# Fly_Buck_Power_Supply_for_Inverter.net
KiCad netlist of a schematic drawn in Altium Designer
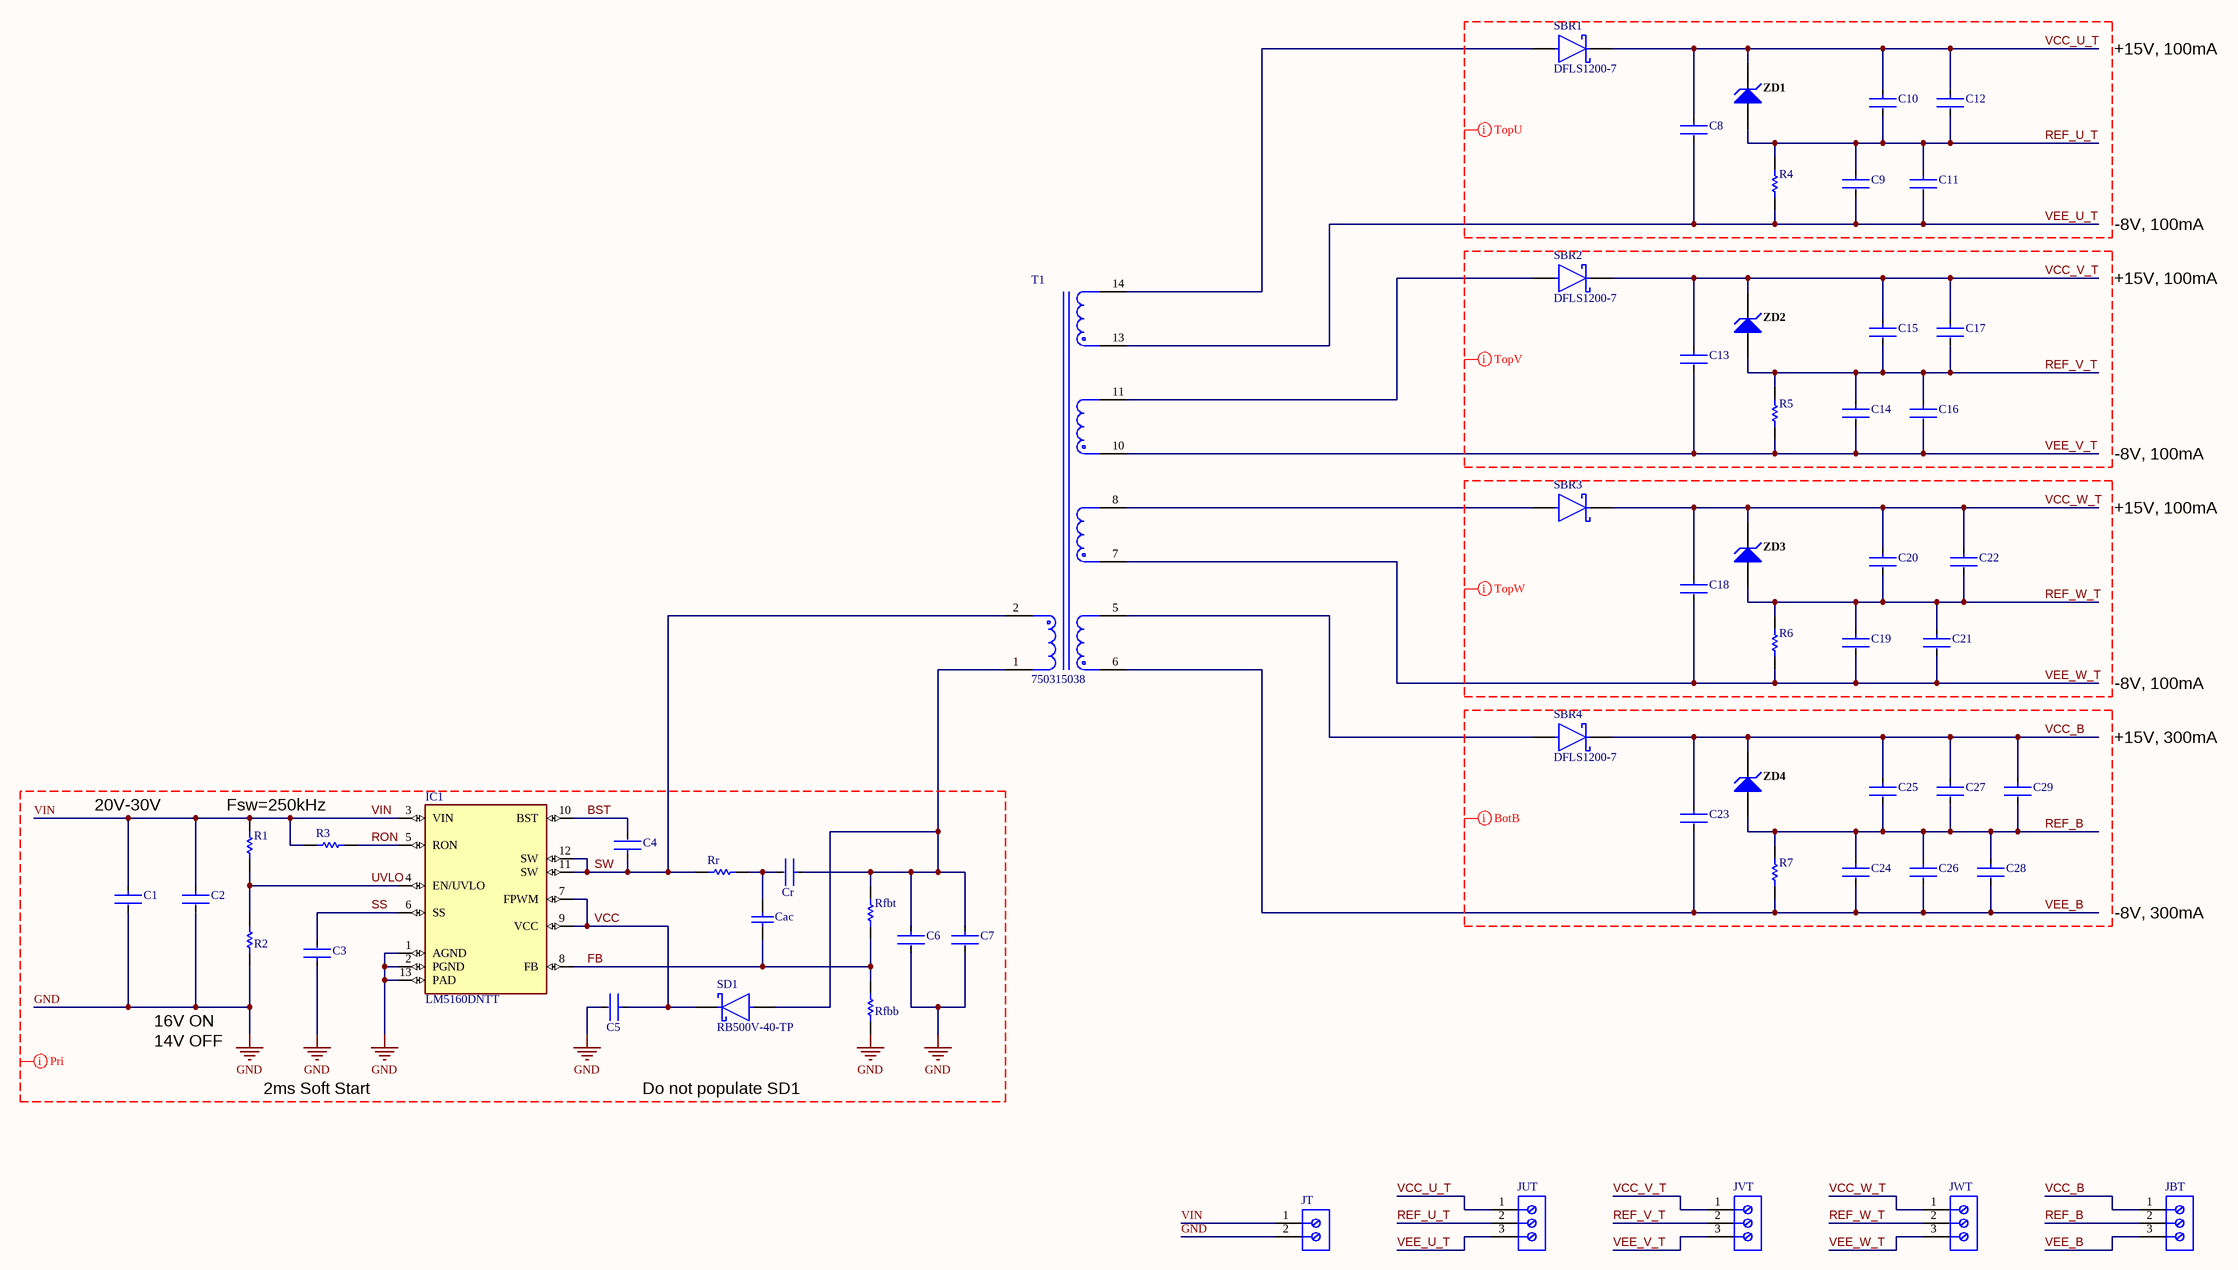
[diagram p0: Fly_Buck_Power_Supply_for_Inverter.SchDoc]

(export (version "E")
  (design (tool "Eeschema 10.0.6"))
  (components
    (comp (ref "C1")
      (value "GRM32ER71H106KA12L")
      (footprint "FP-GRM32-MFG")
      (description "CAP CER 10µF 50V X7R 1210")
      (fields (field (name "TOLERANCE") "10%") (field (name "MANUFACTURER") "Murata"))
      (libsource (lib "Altium Content Vault") (part "11868f565c42a9108669ba33697ecf6"))
    )
    (comp (ref "C2")
      (value "C0603X104K5RACTU")
      (footprint "FP-C0603-CJ-MFG")
      (description "CAP CER 0.1µF 50V X7R 0603")
      (fields (field (name "VOLTAGE") "50V") (field (name "MANUFACTURER") "Kemet"))
      (libsource (lib "Altium Content Vault") (part "11868f565c42a9108669ba33697ecf6"))
    )
    (comp (ref "C3")
      (value "C1608X7R1H103K080AA")
      (footprint "FP-C1608-080-0_1-MFG")
      (description "Multilayer Ceramic Capacitors 0.01µF ±10% 50V X7R SMD 0603")
      (fields (field (name "VOLTAGE") "50V") (field (name "TOLERANCE") "10%"))
      (libsource (lib "Altium Content Vault") (part "236180d848d6139a670b325ea6854c9"))
    )
    (comp (ref "C4")
      (value "C1608X7R1H103K080AA")
      (footprint "FP-C1608-080-0_1-MFG")
      (description "Multilayer Ceramic Capacitors 0.01µF ±10% 50V X7R SMD 0603")
      (fields (field (name "VOLTAGE") "50V") (field (name "TOLERANCE") "10%"))
      (libsource (lib "Altium Content Vault") (part "236180d848d6139a670b325ea6854c9"))
    )
    (comp (ref "C5")
      (value "C1608X5R1E105K080AC")
      (footprint "FP-C1608-080-0_1-MFG")
      (description "Multilayer Ceramic Capacitors 1μF ±10% 25V X5R SMD 0603")
      (fields (field (name "TOLERANCE") "10%"))
      (libsource (lib "Altium Content Vault") (part "236180d848d6139a670b325ea6854c9"))
    )
    (comp (ref "C6")
      (value "GRM32ER71E226KE15L")
      (footprint "FP-GRM32E-0_3-0_2-IPC_B")
      (description "Chip Multilayer Ceramic Capacitors for General Purpose, 1210, 22µF, X7R, 15%, 10%, 25V")
      (fields (field (name "VOLTAGE") "25V") (field (name "TOLERANCE") "10%"))
      (libsource (lib "Altium Content Vault") (part "02cd4be3c70576c341d710602a673aa"))
    )
    (comp (ref "C7")
      (value "GRM32ER71E226KE15L")
      (footprint "FP-GRM32E-0_3-0_2-IPC_B")
      (description "Chip Multilayer Ceramic Capacitors for General Purpose, 1210, 22µF, X7R, 15%, 10%, 25V")
      (fields (field (name "VOLTAGE") "25V") (field (name "TOLERANCE") "10%"))
      (libsource (lib "Altium Content Vault") (part "02cd4be3c70576c341d710602a673aa"))
    )
    (comp (ref "C8")
      (value "GRM32ER71H106KA12L")
      (footprint "FP-GRM32-MFG")
      (description "CAP CER 10µF 50V X7R 1210")
      (fields (field (name "TOLERANCE") "10%") (field (name "MANUFACTURER") "Murata"))
      (libsource (lib "Altium Content Vault") (part "11868f565c42a9108669ba33697ecf6"))
    )
    (comp (ref "C9")
      (value "GRM32ER71E226KE15L")
      (footprint "FP-GRM32E-0_3-0_2-IPC_B")
      (description "Chip Multilayer Ceramic Capacitors for General Purpose, 1210, 22µF, X7R, 15%, 10%, 25V")
      (fields (field (name "VOLTAGE") "25V") (field (name "TOLERANCE") "10%"))
      (libsource (lib "Altium Content Vault") (part "02cd4be3c70576c341d710602a673aa"))
    )
    (comp (ref "C10")
      (value "GRM32ER71E226KE15L")
      (footprint "FP-GRM32E-0_3-0_2-IPC_B")
      (description "Chip Multilayer Ceramic Capacitors for General Purpose, 1210, 22µF, X7R, 15%, 10%, 25V")
      (fields (field (name "VOLTAGE") "25V") (field (name "TOLERANCE") "10%"))
      (libsource (lib "Altium Content Vault") (part "02cd4be3c70576c341d710602a673aa"))
    )
    (comp (ref "C11")
      (value "C0603X104K5RACTU")
      (footprint "FP-C0603-CJ-MFG")
      (description "CAP CER 0.1µF 50V X7R 0603")
      (fields (field (name "VOLTAGE") "50V") (field (name "MANUFACTURER") "Kemet"))
      (libsource (lib "Altium Content Vault") (part "11868f565c42a9108669ba33697ecf6"))
    )
    (comp (ref "C12")
      (value "C0603X104K5RACTU")
      (footprint "FP-C0603-CJ-MFG")
      (description "CAP CER 0.1µF 50V X7R 0603")
      (fields (field (name "VOLTAGE") "50V") (field (name "MANUFACTURER") "Kemet"))
      (libsource (lib "Altium Content Vault") (part "11868f565c42a9108669ba33697ecf6"))
    )
    (comp (ref "C13")
      (value "GRM32ER71H106KA12L")
      (footprint "FP-GRM32-MFG")
      (description "CAP CER 10µF 50V X7R 1210")
      (fields (field (name "TOLERANCE") "10%") (field (name "MANUFACTURER") "Murata"))
      (libsource (lib "Altium Content Vault") (part "11868f565c42a9108669ba33697ecf6"))
    )
    (comp (ref "C14")
      (value "GRM32ER71E226KE15L")
      (footprint "FP-GRM32E-0_3-0_2-IPC_B")
      (description "Chip Multilayer Ceramic Capacitors for General Purpose, 1210, 22µF, X7R, 15%, 10%, 25V")
      (fields (field (name "VOLTAGE") "25V") (field (name "TOLERANCE") "10%"))
      (libsource (lib "Altium Content Vault") (part "02cd4be3c70576c341d710602a673aa"))
    )
    (comp (ref "C15")
      (value "GRM32ER71E226KE15L")
      (footprint "FP-GRM32E-0_3-0_2-IPC_B")
      (description "Chip Multilayer Ceramic Capacitors for General Purpose, 1210, 22µF, X7R, 15%, 10%, 25V")
      (fields (field (name "VOLTAGE") "25V") (field (name "TOLERANCE") "10%"))
      (libsource (lib "Altium Content Vault") (part "02cd4be3c70576c341d710602a673aa"))
    )
    (comp (ref "C16")
      (value "C0603X104K5RACTU")
      (footprint "FP-C0603-CJ-MFG")
      (description "CAP CER 0.1µF 50V X7R 0603")
      (fields (field (name "VOLTAGE") "50V") (field (name "MANUFACTURER") "Kemet"))
      (libsource (lib "Altium Content Vault") (part "11868f565c42a9108669ba33697ecf6"))
    )
    (comp (ref "C17")
      (value "C0603X104K5RACTU")
      (footprint "FP-C0603-CJ-MFG")
      (description "CAP CER 0.1µF 50V X7R 0603")
      (fields (field (name "VOLTAGE") "50V") (field (name "MANUFACTURER") "Kemet"))
      (libsource (lib "Altium Content Vault") (part "11868f565c42a9108669ba33697ecf6"))
    )
    (comp (ref "C18")
      (value "GRM32ER71H106KA12L")
      (footprint "FP-GRM32-MFG")
      (description "CAP CER 10µF 50V X7R 1210")
      (fields (field (name "TOLERANCE") "10%") (field (name "MANUFACTURER") "Murata"))
      (libsource (lib "Altium Content Vault") (part "11868f565c42a9108669ba33697ecf6"))
    )
    (comp (ref "C19")
      (value "GRM32ER71E226KE15L")
      (footprint "FP-GRM32E-0_3-0_2-IPC_B")
      (description "Chip Multilayer Ceramic Capacitors for General Purpose, 1210, 22µF, X7R, 15%, 10%, 25V")
      (fields (field (name "VOLTAGE") "25V") (field (name "TOLERANCE") "10%"))
      (libsource (lib "Altium Content Vault") (part "02cd4be3c70576c341d710602a673aa"))
    )
    (comp (ref "C20")
      (value "GRM32ER71E226KE15L")
      (footprint "FP-GRM32E-0_3-0_2-IPC_B")
      (description "Chip Multilayer Ceramic Capacitors for General Purpose, 1210, 22µF, X7R, 15%, 10%, 25V")
      (fields (field (name "VOLTAGE") "25V") (field (name "TOLERANCE") "10%"))
      (libsource (lib "Altium Content Vault") (part "02cd4be3c70576c341d710602a673aa"))
    )
    (comp (ref "C21")
      (value "C0603X104K5RACTU")
      (footprint "FP-C0603-CJ-MFG")
      (description "CAP CER 0.1µF 50V X7R 0603")
      (fields (field (name "VOLTAGE") "50V") (field (name "MANUFACTURER") "Kemet"))
      (libsource (lib "Altium Content Vault") (part "11868f565c42a9108669ba33697ecf6"))
    )
    (comp (ref "C22")
      (value "C0603X104K5RACTU")
      (footprint "FP-C0603-CJ-MFG")
      (description "CAP CER 0.1µF 50V X7R 0603")
      (fields (field (name "VOLTAGE") "50V") (field (name "MANUFACTURER") "Kemet"))
      (libsource (lib "Altium Content Vault") (part "11868f565c42a9108669ba33697ecf6"))
    )
    (comp (ref "C23")
      (value "GRM32ER71H106KA12L")
      (footprint "FP-GRM32-MFG")
      (description "CAP CER 10µF 50V X7R 1210")
      (fields (field (name "TOLERANCE") "10%") (field (name "MANUFACTURER") "Murata"))
      (libsource (lib "Altium Content Vault") (part "11868f565c42a9108669ba33697ecf6"))
    )
    (comp (ref "C24")
      (value "GRM32ER71E226KE15L")
      (footprint "FP-GRM32E-0_3-0_2-IPC_B")
      (description "Chip Multilayer Ceramic Capacitors for General Purpose, 1210, 22µF, X7R, 15%, 10%, 25V")
      (fields (field (name "VOLTAGE") "25V") (field (name "TOLERANCE") "10%"))
      (libsource (lib "Altium Content Vault") (part "02cd4be3c70576c341d710602a673aa"))
    )
    (comp (ref "C25")
      (value "GRM32ER71E226KE15L")
      (footprint "FP-GRM32E-0_3-0_2-IPC_B")
      (description "Chip Multilayer Ceramic Capacitors for General Purpose, 1210, 22µF, X7R, 15%, 10%, 25V")
      (fields (field (name "VOLTAGE") "25V") (field (name "TOLERANCE") "10%"))
      (libsource (lib "Altium Content Vault") (part "02cd4be3c70576c341d710602a673aa"))
    )
    (comp (ref "C26")
      (value "GRM32ER71E226KE15L")
      (footprint "FP-GRM32E-0_3-0_2-IPC_B")
      (description "Chip Multilayer Ceramic Capacitors for General Purpose, 1210, 22µF, X7R, 15%, 10%, 25V")
      (fields (field (name "VOLTAGE") "25V") (field (name "TOLERANCE") "10%"))
      (libsource (lib "Altium Content Vault") (part "02cd4be3c70576c341d710602a673aa"))
    )
    (comp (ref "C27")
      (value "GRM32ER71E226KE15L")
      (footprint "FP-GRM32E-0_3-0_2-IPC_B")
      (description "Chip Multilayer Ceramic Capacitors for General Purpose, 1210, 22µF, X7R, 15%, 10%, 25V")
      (fields (field (name "VOLTAGE") "25V") (field (name "TOLERANCE") "10%"))
      (libsource (lib "Altium Content Vault") (part "02cd4be3c70576c341d710602a673aa"))
    )
    (comp (ref "C28")
      (value "C0603X104K5RACTU")
      (footprint "FP-C0603-CJ-MFG")
      (description "CAP CER 0.1µF 50V X7R 0603")
      (fields (field (name "VOLTAGE") "50V") (field (name "MANUFACTURER") "Kemet"))
      (libsource (lib "Altium Content Vault") (part "11868f565c42a9108669ba33697ecf6"))
    )
    (comp (ref "C29")
      (value "C0603X104K5RACTU")
      (footprint "FP-C0603-CJ-MFG")
      (description "CAP CER 0.1µF 50V X7R 0603")
      (fields (field (name "VOLTAGE") "50V") (field (name "MANUFACTURER") "Kemet"))
      (libsource (lib "Altium Content Vault") (part "11868f565c42a9108669ba33697ecf6"))
    )
    (comp (ref "Cac")
      (value "C0603X102K5RACTU")
      (footprint "CAPC1608X87X35NL20T15")
      (description "Multilayer Ceramic Capacitor, 1000 pF, 50 V, ± 10%, X7R, 0603 [1608 Metric]")
      (fields (field (name "MANUFACTURER") "Kemet"))
      (libsource (lib "Altium Content Vault") (part "CAP"))
    )
    (comp (ref "Cr")
      (value "C1608X7R1H103K080AA")
      (footprint "FP-C1608-080-0_1-MFG")
      (description "Multilayer Ceramic Capacitors 0.01µF ±10% 50V X7R SMD 0603")
      (fields (field (name "VOLTAGE") "50V") (field (name "TOLERANCE") "10%"))
      (libsource (lib "Altium Content Vault") (part "236180d848d6139a670b325ea6854c9"))
    )
    (comp (ref "IC1")
      (value "LM5160DNTT")
      (footprint "LM5160DNTT:FP-DNT0012B-IPC_B")
      (description "LM5160 wide input 65V, 2A synchronous buck/Fly-Buck converter 12-WSON -40 to 125")
      (libsource (lib "LM5160DNTT") (part "LM5160DNTT"))
    )
    (comp (ref "JBT")
      (value "691214110003")
      (footprint "691214110003")
      (description "Conn Terminal Block 3 POS 3.5mm Solder ST Thru-Hole 10A Box")
      (fields (field (name "VOLTAGE") "300V"))
      (libsource (lib "Altium Content Vault") (part "TBL - 1R - 03P - Screw"))
    )
    (comp (ref "JT")
      (value "691214110002")
      (footprint "691214110002")
      (description "Conn Terminal Block 2 POS 3.5mm Solder ST Thru-Hole 10A Box")
      (fields (field (name "VOLTAGE") "300V"))
      (libsource (lib "Altium Content Vault") (part "TBL - 1R - 02P - Screw"))
    )
    (comp (ref "JUT")
      (value "691214110003")
      (footprint "691214110003")
      (description "Conn Terminal Block 3 POS 3.5mm Solder ST Thru-Hole 10A Box")
      (fields (field (name "VOLTAGE") "300V"))
      (libsource (lib "Altium Content Vault") (part "TBL - 1R - 03P - Screw"))
    )
    (comp (ref "JVT")
      (value "691214110003")
      (footprint "691214110003")
      (description "Conn Terminal Block 3 POS 3.5mm Solder ST Thru-Hole 10A Box")
      (fields (field (name "VOLTAGE") "300V"))
      (libsource (lib "Altium Content Vault") (part "TBL - 1R - 03P - Screw"))
    )
    (comp (ref "JWT")
      (value "691214110003")
      (footprint "691214110003")
      (description "Conn Terminal Block 3 POS 3.5mm Solder ST Thru-Hole 10A Box")
      (fields (field (name "VOLTAGE") "300V"))
      (libsource (lib "Altium Content Vault") (part "TBL - 1R - 03P - Screw"))
    )
    (comp (ref "R1")
      (value "RK73H1JTTD1003F")
      (footprint "RESC1608X55X30ML20T10")
      (description "Res Thick Film 0603 100K Ohm 1% 0.1W(1/10W) ±100ppm/C Pad SMD Automotive T/R")
      (fields (field (name "MANUFACTURER") "KOA Speer"))
      (libsource (lib "Altium Content Vault") (part "RES"))
    )
    (comp (ref "R2")
      (value "CRCW06038K45FKEA")
      (footprint "RESC1609X50X30LL10T20")
      (description "SMD Chip Resistor, 8.45K Ohm, ± 1%, 100 mW, 0603 [1608 Metric], Thick Film, General Purpose")
      (fields (field (name "MANUFACTURER") "Vishay Dale"))
      (libsource (lib "Altium Content Vault") (part "RES"))
    )
    (comp (ref "R3")
      (value "RC0603FR-07453RL")
      (footprint "RESC1608X55X25NL10T15")
      (description "SMD Chip Resistor, 453 Ohm, ± 1%, 100 mW, 0603 [1608 Metric], Thick Film, General Purpos")
      (fields (field (name "MANUFACTURER") "Yageo"))
      (libsource (lib "Altium Content Vault") (part "RES"))
    )
    (comp (ref "R4")
      (value "ERJ-6ENF5110V")
      (footprint "RESC2013X70X40ML20T20")
      (description "SMD Chip Resistor, 511 Ohm, ± 1%, 125 mW, 0805 [2012 Metric], Thick Film, Precision")
      (fields (field (name "MANUFACTURER") "Panasonic"))
      (libsource (lib "Altium Content Vault") (part "RES"))
    )
    (comp (ref "R5")
      (value "ERJ-6ENF5110V")
      (footprint "RESC2013X70X40ML20T20")
      (description "SMD Chip Resistor, 511 Ohm, ± 1%, 125 mW, 0805 [2012 Metric], Thick Film, Precision")
      (fields (field (name "MANUFACTURER") "Panasonic"))
      (libsource (lib "Altium Content Vault") (part "RES"))
    )
    (comp (ref "R6")
      (value "ERJ-6ENF5110V")
      (footprint "RESC2013X70X40ML20T20")
      (description "SMD Chip Resistor, 511 Ohm, ± 1%, 125 mW, 0805 [2012 Metric], Thick Film, Precision")
      (fields (field (name "MANUFACTURER") "Panasonic"))
      (libsource (lib "Altium Content Vault") (part "RES"))
    )
    (comp (ref "R7")
      (value "ERJ-6ENF5110V")
      (footprint "RESC2013X70X40ML20T20")
      (description "SMD Chip Resistor, 511 Ohm, ± 1%, 125 mW, 0805 [2012 Metric], Thick Film, Precision")
      (fields (field (name "MANUFACTURER") "Panasonic"))
      (libsource (lib "Altium Content Vault") (part "RES"))
    )
    (comp (ref "Rfbb")
      (value "ERA3AEB2052V")
      (footprint "RESC1608X55X30ML20T20")
      (description "Res Thin Film 0603 20.5K Ohm 0.1% 0.1W(1/10W) ±25ppm/C Pad SMD Automotive T/R")
      (fields (field (name "MANUFACTURER") "Panasonic"))
      (libsource (lib "Altium Content Vault") (part "RES"))
    )
    (comp (ref "Rfbt")
      (value "ERJ-3EKF8662V")
      (footprint "RESC1608X55X30NL15T15")
      (fields (field (name "MANUFACTURER") "Panasonic"))
      (libsource (lib "Altium Content Vault") (part "RES"))
    )
    (comp (ref "Rr")
      (value "ERA3AEB2052V")
      (footprint "RESC1608X55X30ML20T20")
      (description "Res Thin Film 0603 20.5K Ohm 0.1% 0.1W(1/10W) ±25ppm/C Pad SMD Automotive T/R")
      (fields (field (name "MANUFACTURER") "Panasonic"))
      (libsource (lib "Altium Content Vault") (part "RES"))
    )
    (comp (ref "SBR1")
      (value "DFLS1200-7")
      (footprint "FP-PowerDI123-MFG")
      (description "Rectifier Diode, Schottky, 200V, 1A")
      (fields
        (field (name "MANUFACTURER") "Diodes Inc.")
        (field (name "OCTOPART") "https://octopart.com/dfls1200-7-diodes+inc.-13134059")
      )
      (libsource (lib "Altium Content Vault") (part "1d6ec82d83fb6aee721767c19dac4b9"))
    )
    (comp (ref "SBR2")
      (value "DFLS1200-7")
      (footprint "FP-PowerDI123-MFG")
      (description "Rectifier Diode, Schottky, 200V, 1A")
      (fields
        (field (name "MANUFACTURER") "Diodes Inc.")
        (field (name "OCTOPART") "https://octopart.com/dfls1200-7-diodes+inc.-13134059")
      )
      (libsource (lib "Altium Content Vault") (part "1d6ec82d83fb6aee721767c19dac4b9"))
    )
    (comp (ref "SBR3")
      (value "DFLS1200-7")
      (footprint "FP-PowerDI123-MFG")
      (description "Rectifier Diode, Schottky, 200V, 1A")
      (fields
        (field (name "MANUFACTURER") "Diodes Inc.")
        (field (name "OCTOPART") "https://octopart.com/dfls1200-7-diodes+inc.-13134059")
      )
      (libsource (lib "Altium Content Vault") (part "1d6ec82d83fb6aee721767c19dac4b9"))
    )
    (comp (ref "SBR4")
      (value "DFLS1200-7")
      (footprint "FP-PowerDI123-MFG")
      (description "Rectifier Diode, Schottky, 200V, 1A")
      (fields
        (field (name "MANUFACTURER") "Diodes Inc.")
        (field (name "OCTOPART") "https://octopart.com/dfls1200-7-diodes+inc.-13134059")
      )
      (libsource (lib "Altium Content Vault") (part "1d6ec82d83fb6aee721767c19dac4b9"))
    )
    (comp (ref "SD1")
      (value "RB500V-40-TP")
      (footprint "FP-SOD-323-MFG")
      (description "Rectifier Diode Schottky 45V 0.1A")
      (libsource (lib "Altium Content Vault") (part "1d6ec82d83fb6aee721767c19dac4b9"))
    )
    (comp (ref "T1")
      (value "750315038")
      (footprint "PCBComponent_1")
      (libsource (lib "750315038") (part "750315038"))
    )
    (comp (ref "ZD1")
      (value "MMSZ5245B-E3-08")
      (footprint "VISH-SOD-123-2_V")
      (description "MMSZ5245 Series 15V ±5% 500 mW SMT Small Signal Zener Diode - SOD-123")
      (fields (field (name "MANUFACTURER") "Vishay Semiconductor") (field (name "TOLERANCE") "+/- 5%"))
      (libsource (lib "Altium Content Vault") (part "VISH-DZEN_A1K2-2"))
    )
    (comp (ref "ZD2")
      (value "MMSZ5245B-E3-08")
      (footprint "VISH-SOD-123-2_V")
      (description "MMSZ5245 Series 15V ±5% 500 mW SMT Small Signal Zener Diode - SOD-123")
      (fields (field (name "MANUFACTURER") "Vishay Semiconductor") (field (name "TOLERANCE") "+/- 5%"))
      (libsource (lib "Altium Content Vault") (part "VISH-DZEN_A1K2-2"))
    )
    (comp (ref "ZD3")
      (value "MMSZ5245B-E3-08")
      (footprint "VISH-SOD-123-2_V")
      (description "MMSZ5245 Series 15V ±5% 500 mW SMT Small Signal Zener Diode - SOD-123")
      (fields (field (name "MANUFACTURER") "Vishay Semiconductor") (field (name "TOLERANCE") "+/- 5%"))
      (libsource (lib "Altium Content Vault") (part "VISH-DZEN_A1K2-2"))
    )
    (comp (ref "ZD4")
      (value "MMSZ5245B-E3-08")
      (footprint "VISH-SOD-123-2_V")
      (description "MMSZ5245 Series 15V ±5% 500 mW SMT Small Signal Zener Diode - SOD-123")
      (fields (field (name "MANUFACTURER") "Vishay Semiconductor") (field (name "TOLERANCE") "+/- 5%"))
      (libsource (lib "Altium Content Vault") (part "VISH-DZEN_A1K2-2"))
    )
  )
  (nets
    (net (code "1") (name "/BST") (class "Default")
      (node (ref "C4") (pin "1") (pinfunction "1_1") (pintype "passive"))
      (node (ref "IC1") (pin "10") (pinfunction "BST_10") (pintype "bidirectional"))
    )
    (net (code "2") (name "/FB") (class "Default")
      (node (ref "Cac") (pin "2") (pinfunction "2_2") (pintype "passive"))
      (node (ref "IC1") (pin "8") (pinfunction "FB_8") (pintype "bidirectional"))
      (node (ref "Rfbb") (pin "1") (pinfunction "1_1") (pintype "passive"))
      (node (ref "Rfbt") (pin "2") (pinfunction "2_2") (pintype "passive"))
    )
    (net (code "3") (name "/REF_B") (class "Default")
      (node (ref "C24") (pin "1") (pinfunction "1_1") (pintype "passive"))
      (node (ref "C25") (pin "2") (pinfunction "2_2") (pintype "passive"))
      (node (ref "C26") (pin "1") (pinfunction "1_1") (pintype "passive"))
      (node (ref "C27") (pin "2") (pinfunction "2_2") (pintype "passive"))
      (node (ref "C28") (pin "1") (pinfunction "1_1") (pintype "passive"))
      (node (ref "C29") (pin "2") (pinfunction "2_2") (pintype "passive"))
      (node (ref "JBT") (pin "2") (pinfunction "2_2") (pintype "passive"))
      (node (ref "R7") (pin "1") (pinfunction "1_1") (pintype "passive"))
      (node (ref "ZD4") (pin "1") (pinfunction "A_1") (pintype "passive"))
    )
    (net (code "4") (name "/REF_U_T") (class "Default")
      (node (ref "C10") (pin "2") (pinfunction "2_2") (pintype "passive"))
      (node (ref "C11") (pin "1") (pinfunction "1_1") (pintype "passive"))
      (node (ref "C12") (pin "2") (pinfunction "2_2") (pintype "passive"))
      (node (ref "C9") (pin "1") (pinfunction "1_1") (pintype "passive"))
      (node (ref "JUT") (pin "2") (pinfunction "2_2") (pintype "passive"))
      (node (ref "R4") (pin "1") (pinfunction "1_1") (pintype "passive"))
      (node (ref "ZD1") (pin "1") (pinfunction "A_1") (pintype "passive"))
    )
    (net (code "5") (name "/REF_V_T") (class "Default")
      (node (ref "C14") (pin "1") (pinfunction "1_1") (pintype "passive"))
      (node (ref "C15") (pin "2") (pinfunction "2_2") (pintype "passive"))
      (node (ref "C16") (pin "1") (pinfunction "1_1") (pintype "passive"))
      (node (ref "C17") (pin "2") (pinfunction "2_2") (pintype "passive"))
      (node (ref "JVT") (pin "2") (pinfunction "2_2") (pintype "passive"))
      (node (ref "R5") (pin "1") (pinfunction "1_1") (pintype "passive"))
      (node (ref "ZD2") (pin "1") (pinfunction "A_1") (pintype "passive"))
    )
    (net (code "6") (name "/REF_W_T") (class "Default")
      (node (ref "C19") (pin "1") (pinfunction "1_1") (pintype "passive"))
      (node (ref "C20") (pin "2") (pinfunction "2_2") (pintype "passive"))
      (node (ref "C21") (pin "1") (pinfunction "1_1") (pintype "passive"))
      (node (ref "C22") (pin "2") (pinfunction "2_2") (pintype "passive"))
      (node (ref "JWT") (pin "2") (pinfunction "2_2") (pintype "passive"))
      (node (ref "R6") (pin "1") (pinfunction "1_1") (pintype "passive"))
      (node (ref "ZD3") (pin "1") (pinfunction "A_1") (pintype "passive"))
    )
    (net (code "7") (name "/RON") (class "Default")
      (node (ref "IC1") (pin "5") (pinfunction "RON_5") (pintype "bidirectional"))
      (node (ref "R3") (pin "2") (pinfunction "2_2") (pintype "passive"))
    )
    (net (code "8") (name "/SS") (class "Default")
      (node (ref "C3") (pin "1") (pinfunction "1_1") (pintype "passive"))
      (node (ref "IC1") (pin "6") (pinfunction "SS_6") (pintype "bidirectional"))
    )
    (net (code "9") (name "/SW") (class "Default")
      (node (ref "C4") (pin "2") (pinfunction "2_2") (pintype "passive"))
      (node (ref "IC1") (pin "11") (pinfunction "SW_11") (pintype "bidirectional"))
      (node (ref "IC1") (pin "12") (pinfunction "SW_12") (pintype "bidirectional"))
      (node (ref "Rr") (pin "1") (pinfunction "1_1") (pintype "passive"))
      (node (ref "T1") (pin "2") (pinfunction "Secondary_Dot_2") (pintype "passive"))
    )
    (net (code "10") (name "/UVLO") (class "Default")
      (node (ref "IC1") (pin "4") (pinfunction "EN/UVLO_4") (pintype "bidirectional"))
      (node (ref "R1") (pin "2") (pinfunction "2_2") (pintype "passive"))
      (node (ref "R2") (pin "1") (pinfunction "1_1") (pintype "passive"))
    )
    (net (code "11") (name "/VCC") (class "Default")
      (node (ref "C5") (pin "2") (pinfunction "2_2") (pintype "passive"))
      (node (ref "IC1") (pin "7") (pinfunction "FPWM_7") (pintype "bidirectional"))
      (node (ref "IC1") (pin "9") (pinfunction "VCC_9") (pintype "bidirectional"))
      (node (ref "SD1") (pin "1") (pinfunction "C_1") (pintype "passive"))
    )
    (net (code "12") (name "/VCC_B") (class "Default")
      (node (ref "C23") (pin "1") (pinfunction "1_1") (pintype "passive"))
      (node (ref "C25") (pin "1") (pinfunction "1_1") (pintype "passive"))
      (node (ref "C27") (pin "1") (pinfunction "1_1") (pintype "passive"))
      (node (ref "C29") (pin "1") (pinfunction "1_1") (pintype "passive"))
      (node (ref "JBT") (pin "1") (pinfunction "1_1") (pintype "passive"))
      (node (ref "SBR4") (pin "1") (pinfunction "C_1") (pintype "passive"))
      (node (ref "ZD4") (pin "2") (pinfunction "K_2") (pintype "passive"))
    )
    (net (code "13") (name "/VCC_U_T") (class "Default")
      (node (ref "C10") (pin "1") (pinfunction "1_1") (pintype "passive"))
      (node (ref "C12") (pin "1") (pinfunction "1_1") (pintype "passive"))
      (node (ref "C8") (pin "1") (pinfunction "1_1") (pintype "passive"))
      (node (ref "JUT") (pin "1") (pinfunction "1_1") (pintype "passive"))
      (node (ref "SBR1") (pin "1") (pinfunction "C_1") (pintype "passive"))
      (node (ref "ZD1") (pin "2") (pinfunction "K_2") (pintype "passive"))
    )
    (net (code "14") (name "/VCC_V_T") (class "Default")
      (node (ref "C13") (pin "1") (pinfunction "1_1") (pintype "passive"))
      (node (ref "C15") (pin "1") (pinfunction "1_1") (pintype "passive"))
      (node (ref "C17") (pin "1") (pinfunction "1_1") (pintype "passive"))
      (node (ref "JVT") (pin "1") (pinfunction "1_1") (pintype "passive"))
      (node (ref "SBR2") (pin "1") (pinfunction "C_1") (pintype "passive"))
      (node (ref "ZD2") (pin "2") (pinfunction "K_2") (pintype "passive"))
    )
    (net (code "15") (name "/VCC_W_T") (class "Default")
      (node (ref "C18") (pin "1") (pinfunction "1_1") (pintype "passive"))
      (node (ref "C20") (pin "1") (pinfunction "1_1") (pintype "passive"))
      (node (ref "C22") (pin "1") (pinfunction "1_1") (pintype "passive"))
      (node (ref "JWT") (pin "1") (pinfunction "1_1") (pintype "passive"))
      (node (ref "SBR3") (pin "1") (pinfunction "C_1") (pintype "passive"))
      (node (ref "ZD3") (pin "2") (pinfunction "K_2") (pintype "passive"))
    )
    (net (code "16") (name "/VEE_B") (class "Default")
      (node (ref "C23") (pin "2") (pinfunction "2_2") (pintype "passive"))
      (node (ref "C24") (pin "2") (pinfunction "2_2") (pintype "passive"))
      (node (ref "C26") (pin "2") (pinfunction "2_2") (pintype "passive"))
      (node (ref "C28") (pin "2") (pinfunction "2_2") (pintype "passive"))
      (node (ref "JBT") (pin "3") (pinfunction "3_3") (pintype "passive"))
      (node (ref "R7") (pin "2") (pinfunction "2_2") (pintype "passive"))
      (node (ref "T1") (pin "6") (pinfunction "Secondary_Dot_6") (pintype "passive"))
    )
    (net (code "17") (name "/VEE_U_T") (class "Default")
      (node (ref "C11") (pin "2") (pinfunction "2_2") (pintype "passive"))
      (node (ref "C8") (pin "2") (pinfunction "2_2") (pintype "passive"))
      (node (ref "C9") (pin "2") (pinfunction "2_2") (pintype "passive"))
      (node (ref "JUT") (pin "3") (pinfunction "3_3") (pintype "passive"))
      (node (ref "R4") (pin "2") (pinfunction "2_2") (pintype "passive"))
      (node (ref "T1") (pin "13") (pinfunction "Secondary_Dot_13") (pintype "passive"))
    )
    (net (code "18") (name "/VEE_V_T") (class "Default")
      (node (ref "C13") (pin "2") (pinfunction "2_2") (pintype "passive"))
      (node (ref "C14") (pin "2") (pinfunction "2_2") (pintype "passive"))
      (node (ref "C16") (pin "2") (pinfunction "2_2") (pintype "passive"))
      (node (ref "JVT") (pin "3") (pinfunction "3_3") (pintype "passive"))
      (node (ref "R5") (pin "2") (pinfunction "2_2") (pintype "passive"))
      (node (ref "T1") (pin "10") (pinfunction "Secondary_Dot_10") (pintype "passive"))
    )
    (net (code "19") (name "/VEE_W_T") (class "Default")
      (node (ref "C18") (pin "2") (pinfunction "2_2") (pintype "passive"))
      (node (ref "C19") (pin "2") (pinfunction "2_2") (pintype "passive"))
      (node (ref "C21") (pin "2") (pinfunction "2_2") (pintype "passive"))
      (node (ref "JWT") (pin "3") (pinfunction "3_3") (pintype "passive"))
      (node (ref "R6") (pin "2") (pinfunction "2_2") (pintype "passive"))
      (node (ref "T1") (pin "7") (pinfunction "Secondary_Dot_7") (pintype "passive"))
    )
    (net (code "20") (name "/VIN") (class "Default")
      (node (ref "C1") (pin "1") (pinfunction "1_1") (pintype "passive"))
      (node (ref "C2") (pin "1") (pinfunction "1_1") (pintype "passive"))
      (node (ref "IC1") (pin "3") (pinfunction "VIN_3") (pintype "bidirectional"))
      (node (ref "JT") (pin "1") (pinfunction "1_1") (pintype "passive"))
      (node (ref "R1") (pin "1") (pinfunction "1_1") (pintype "passive"))
      (node (ref "R3") (pin "1") (pinfunction "1_1") (pintype "passive"))
    )
    (net (code "21") (name "GND") (class "Default")
      (node (ref "C1") (pin "2") (pinfunction "2_2") (pintype "passive"))
      (node (ref "C2") (pin "2") (pinfunction "2_2") (pintype "passive"))
      (node (ref "C3") (pin "2") (pinfunction "2_2") (pintype "passive"))
      (node (ref "C5") (pin "1") (pinfunction "1_1") (pintype "passive"))
      (node (ref "C6") (pin "2") (pinfunction "2_2") (pintype "passive"))
      (node (ref "C7") (pin "2") (pinfunction "2_2") (pintype "passive"))
      (node (ref "IC1") (pin "1") (pinfunction "AGND_1") (pintype "bidirectional"))
      (node (ref "IC1") (pin "13") (pinfunction "PAD_13") (pintype "bidirectional"))
      (node (ref "IC1") (pin "2") (pinfunction "PGND_2") (pintype "bidirectional"))
      (node (ref "JT") (pin "2") (pinfunction "2_2") (pintype "passive"))
      (node (ref "R2") (pin "2") (pinfunction "2_2") (pintype "passive"))
      (node (ref "Rfbb") (pin "2") (pinfunction "2_2") (pintype "passive"))
    )
    (net (code "22") (name "Net-(Cac-Pad1)") (class "Default")
      (node (ref "Cac") (pin "1") (pinfunction "1_1") (pintype "passive"))
      (node (ref "Cr") (pin "1") (pinfunction "1_1") (pintype "passive"))
      (node (ref "Rr") (pin "2") (pinfunction "2_2") (pintype "passive"))
    )
    (net (code "23") (name "Net-(SBR1-A)") (class "Default")
      (node (ref "SBR1") (pin "2") (pinfunction "A_2") (pintype "passive"))
      (node (ref "T1") (pin "14") (pinfunction "Primary_Dot_14") (pintype "passive"))
    )
    (net (code "24") (name "Net-(SBR2-A)") (class "Default")
      (node (ref "SBR2") (pin "2") (pinfunction "A_2") (pintype "passive"))
      (node (ref "T1") (pin "11") (pinfunction "Primary_Dot_11") (pintype "passive"))
    )
    (net (code "25") (name "Net-(SBR3-A)") (class "Default")
      (node (ref "SBR3") (pin "2") (pinfunction "A_2") (pintype "passive"))
      (node (ref "T1") (pin "8") (pinfunction "Primary_Dot_8") (pintype "passive"))
    )
    (net (code "26") (name "Net-(SBR4-A)") (class "Default")
      (node (ref "SBR4") (pin "2") (pinfunction "A_2") (pintype "passive"))
      (node (ref "T1") (pin "5") (pinfunction "Primary_Dot_5") (pintype "passive"))
    )
    (net (code "27") (name "Net-(SD1-A)") (class "Default")
      (node (ref "C6") (pin "1") (pinfunction "1_1") (pintype "passive"))
      (node (ref "C7") (pin "1") (pinfunction "1_1") (pintype "passive"))
      (node (ref "Cr") (pin "2") (pinfunction "2_2") (pintype "passive"))
      (node (ref "Rfbt") (pin "1") (pinfunction "1_1") (pintype "passive"))
      (node (ref "SD1") (pin "2") (pinfunction "A_2") (pintype "passive"))
      (node (ref "T1") (pin "1") (pinfunction "Primary_Dot_1") (pintype "passive"))
    )
  )
)
